# Sheet1.net
KiCad netlist of a schematic drawn in Altium Designer
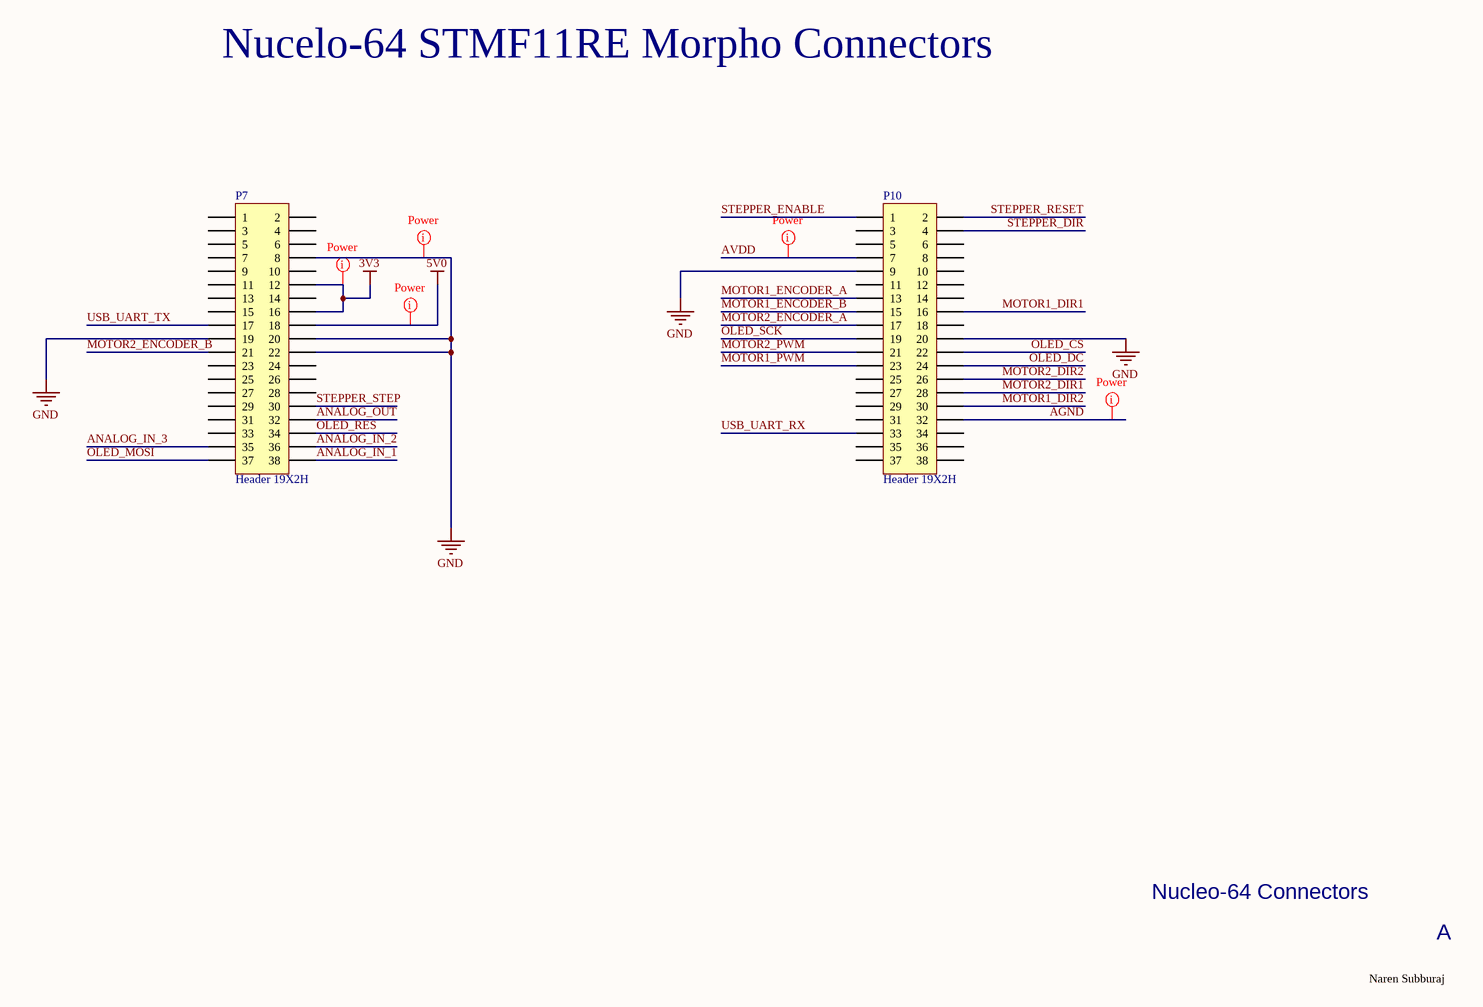
[diagram p0: Sheet1.SchDoc]

(export (version "E")
  (design (tool "Eeschema 10.0.6"))
  (components
    (comp (ref "P7")
      (value "Header 19X2H")
      (footprint "PPPC192LFBN-RC")
      (description "38 Position Header Connector 0.100in (2.54mm) Through Hole Gold")
      (fields (field (name "MPN") "PPPC192LFBN-RC"))
      (libsource (lib "esd_library") (part "Header 19X2H"))
    )
    (comp (ref "P10")
      (value "Header 19X2H")
      (footprint "PPPC192LFBN-RC")
      (description "38 Position Header Connector 0.100in (2.54mm) Through Hole Gold")
      (fields (field (name "MPN") "PPPC192LFBN-RC"))
      (libsource (lib "esd_library") (part "Header 19X2H"))
    )
  )
  (nets
    (net (code "1") (name "/AGND") (class "Default")
      (node (ref "P10") (pin "32") (pinfunction "32_32") (pintype "passive"))
    )
    (net (code "2") (name "/ANALOG_IN_1") (class "Default")
      (node (ref "P7") (pin "38") (pinfunction "38_38") (pintype "passive"))
    )
    (net (code "3") (name "/ANALOG_IN_2") (class "Default")
      (node (ref "P7") (pin "36") (pinfunction "36_36") (pintype "passive"))
    )
    (net (code "4") (name "/ANALOG_IN_3") (class "Default")
      (node (ref "P7") (pin "35") (pinfunction "35_35") (pintype "passive"))
    )
    (net (code "5") (name "/ANALOG_OUT") (class "Default")
      (node (ref "P7") (pin "32") (pinfunction "32_32") (pintype "passive"))
    )
    (net (code "6") (name "/AVDD") (class "Default")
      (node (ref "P10") (pin "7") (pinfunction "7_7") (pintype "passive"))
    )
    (net (code "7") (name "/MOTOR1_DIR1") (class "Default")
      (node (ref "P10") (pin "16") (pinfunction "16_16") (pintype "passive"))
    )
    (net (code "8") (name "/MOTOR1_DIR2") (class "Default")
      (node (ref "P10") (pin "30") (pinfunction "30_30") (pintype "passive"))
    )
    (net (code "9") (name "/MOTOR1_ENCODER_A") (class "Default")
      (node (ref "P10") (pin "13") (pinfunction "13_13") (pintype "passive"))
    )
    (net (code "10") (name "/MOTOR1_ENCODER_B") (class "Default")
      (node (ref "P10") (pin "15") (pinfunction "15_15") (pintype "passive"))
    )
    (net (code "11") (name "/MOTOR1_PWM") (class "Default")
      (node (ref "P10") (pin "23") (pinfunction "23_23") (pintype "passive"))
    )
    (net (code "12") (name "/MOTOR2_DIR1") (class "Default")
      (node (ref "P10") (pin "28") (pinfunction "28_28") (pintype "passive"))
    )
    (net (code "13") (name "/MOTOR2_DIR2") (class "Default")
      (node (ref "P10") (pin "26") (pinfunction "26_26") (pintype "passive"))
    )
    (net (code "14") (name "/MOTOR2_ENCODER_A") (class "Default")
      (node (ref "P10") (pin "17") (pinfunction "17_17") (pintype "passive"))
    )
    (net (code "15") (name "/MOTOR2_ENCODER_B") (class "Default")
      (node (ref "P7") (pin "21") (pinfunction "21_21") (pintype "passive"))
    )
    (net (code "16") (name "/MOTOR2_PWM") (class "Default")
      (node (ref "P10") (pin "21") (pinfunction "21_21") (pintype "passive"))
    )
    (net (code "17") (name "/OLED_CS") (class "Default")
      (node (ref "P10") (pin "22") (pinfunction "22_22") (pintype "passive"))
    )
    (net (code "18") (name "/OLED_DC") (class "Default")
      (node (ref "P10") (pin "24") (pinfunction "24_24") (pintype "passive"))
    )
    (net (code "19") (name "/OLED_MOSI") (class "Default")
      (node (ref "P7") (pin "37") (pinfunction "37_37") (pintype "passive"))
    )
    (net (code "20") (name "/OLED_RES") (class "Default")
      (node (ref "P7") (pin "34") (pinfunction "34_34") (pintype "passive"))
    )
    (net (code "21") (name "/OLED_SCK") (class "Default")
      (node (ref "P10") (pin "19") (pinfunction "19_19") (pintype "passive"))
    )
    (net (code "22") (name "/STEPPER_DIR") (class "Default")
      (node (ref "P10") (pin "4") (pinfunction "4_4") (pintype "passive"))
    )
    (net (code "23") (name "/STEPPER_ENABLE") (class "Default")
      (node (ref "P10") (pin "1") (pinfunction "1_1") (pintype "passive"))
    )
    (net (code "24") (name "/STEPPER_RESET") (class "Default")
      (node (ref "P10") (pin "2") (pinfunction "2_2") (pintype "passive"))
    )
    (net (code "25") (name "/STEPPER_STEP") (class "Default")
      (node (ref "P7") (pin "30") (pinfunction "30_30") (pintype "passive"))
    )
    (net (code "26") (name "/USB_UART_RX") (class "Default")
      (node (ref "P10") (pin "33") (pinfunction "33_33") (pintype "passive"))
    )
    (net (code "27") (name "/USB_UART_TX") (class "Default")
      (node (ref "P7") (pin "17") (pinfunction "17_17") (pintype "passive"))
    )
    (net (code "28") (name "3V3") (class "Default")
      (node (ref "P7") (pin "12") (pinfunction "12_12") (pintype "passive"))
      (node (ref "P7") (pin "16") (pinfunction "16_16") (pintype "passive"))
    )
    (net (code "29") (name "5V0") (class "Default")
      (node (ref "P7") (pin "18") (pinfunction "18_18") (pintype "passive"))
    )
    (net (code "30") (name "GND") (class "Default")
      (node (ref "P10") (pin "20") (pinfunction "20_20") (pintype "passive"))
      (node (ref "P10") (pin "9") (pinfunction "9_9") (pintype "passive"))
      (node (ref "P7") (pin "19") (pinfunction "19_19") (pintype "passive"))
      (node (ref "P7") (pin "20") (pinfunction "20_20") (pintype "passive"))
      (node (ref "P7") (pin "22") (pinfunction "22_22") (pintype "passive"))
      (node (ref "P7") (pin "8") (pinfunction "8_8") (pintype "passive"))
    )
    (net (code "31") (name "unconnected-(P7-Pad1)") (class "Default")
      (node (ref "P7") (pin "1") (pinfunction "1_1") (pintype "passive"))
    )
    (net (code "32") (name "unconnected-(P7-Pad2)") (class "Default")
      (node (ref "P7") (pin "2") (pinfunction "2_2") (pintype "passive"))
    )
    (net (code "33") (name "unconnected-(P7-Pad3)") (class "Default")
      (node (ref "P7") (pin "3") (pinfunction "3_3") (pintype "passive"))
    )
    (net (code "34") (name "unconnected-(P7-Pad4)") (class "Default")
      (node (ref "P7") (pin "4") (pinfunction "4_4") (pintype "passive"))
    )
    (net (code "35") (name "unconnected-(P7-Pad5)") (class "Default")
      (node (ref "P7") (pin "5") (pinfunction "5_5") (pintype "passive"))
    )
    (net (code "36") (name "unconnected-(P7-Pad6)") (class "Default")
      (node (ref "P7") (pin "6") (pinfunction "6_6") (pintype "passive"))
    )
    (net (code "37") (name "unconnected-(P7-Pad7)") (class "Default")
      (node (ref "P7") (pin "7") (pinfunction "7_7") (pintype "passive"))
    )
    (net (code "38") (name "unconnected-(P7-Pad9)") (class "Default")
      (node (ref "P7") (pin "9") (pinfunction "9_9") (pintype "passive"))
    )
    (net (code "39") (name "unconnected-(P7-Pad10)") (class "Default")
      (node (ref "P7") (pin "10") (pinfunction "10_10") (pintype "passive"))
    )
    (net (code "40") (name "unconnected-(P7-Pad11)") (class "Default")
      (node (ref "P7") (pin "11") (pinfunction "11_11") (pintype "passive"))
    )
    (net (code "41") (name "unconnected-(P7-Pad13)") (class "Default")
      (node (ref "P7") (pin "13") (pinfunction "13_13") (pintype "passive"))
    )
    (net (code "42") (name "unconnected-(P7-Pad14)") (class "Default")
      (node (ref "P7") (pin "14") (pinfunction "14_14") (pintype "passive"))
    )
    (net (code "43") (name "unconnected-(P7-Pad15)") (class "Default")
      (node (ref "P7") (pin "15") (pinfunction "15_15") (pintype "passive"))
    )
    (net (code "44") (name "unconnected-(P7-Pad23)") (class "Default")
      (node (ref "P7") (pin "23") (pinfunction "23_23") (pintype "passive"))
    )
    (net (code "45") (name "unconnected-(P7-Pad24)") (class "Default")
      (node (ref "P7") (pin "24") (pinfunction "24_24") (pintype "passive"))
    )
    (net (code "46") (name "unconnected-(P7-Pad25)") (class "Default")
      (node (ref "P7") (pin "25") (pinfunction "25_25") (pintype "passive"))
    )
    (net (code "47") (name "unconnected-(P7-Pad26)") (class "Default")
      (node (ref "P7") (pin "26") (pinfunction "26_26") (pintype "passive"))
    )
    (net (code "48") (name "unconnected-(P7-Pad27)") (class "Default")
      (node (ref "P7") (pin "27") (pinfunction "27_27") (pintype "passive"))
    )
    (net (code "49") (name "unconnected-(P7-Pad28)") (class "Default")
      (node (ref "P7") (pin "28") (pinfunction "28_28") (pintype "passive"))
    )
    (net (code "50") (name "unconnected-(P7-Pad29)") (class "Default")
      (node (ref "P7") (pin "29") (pinfunction "29_29") (pintype "passive"))
    )
    (net (code "51") (name "unconnected-(P7-Pad31)") (class "Default")
      (node (ref "P7") (pin "31") (pinfunction "31_31") (pintype "passive"))
    )
    (net (code "52") (name "unconnected-(P7-Pad33)") (class "Default")
      (node (ref "P7") (pin "33") (pinfunction "33_33") (pintype "passive"))
    )
    (net (code "53") (name "unconnected-(P10-Pad3)") (class "Default")
      (node (ref "P10") (pin "3") (pinfunction "3_3") (pintype "passive"))
    )
    (net (code "54") (name "unconnected-(P10-Pad5)") (class "Default")
      (node (ref "P10") (pin "5") (pinfunction "5_5") (pintype "passive"))
    )
    (net (code "55") (name "unconnected-(P10-Pad6)") (class "Default")
      (node (ref "P10") (pin "6") (pinfunction "6_6") (pintype "passive"))
    )
    (net (code "56") (name "unconnected-(P10-Pad8)") (class "Default")
      (node (ref "P10") (pin "8") (pinfunction "8_8") (pintype "passive"))
    )
    (net (code "57") (name "unconnected-(P10-Pad10)") (class "Default")
      (node (ref "P10") (pin "10") (pinfunction "10_10") (pintype "passive"))
    )
    (net (code "58") (name "unconnected-(P10-Pad11)") (class "Default")
      (node (ref "P10") (pin "11") (pinfunction "11_11") (pintype "passive"))
    )
    (net (code "59") (name "unconnected-(P10-Pad12)") (class "Default")
      (node (ref "P10") (pin "12") (pinfunction "12_12") (pintype "passive"))
    )
    (net (code "60") (name "unconnected-(P10-Pad14)") (class "Default")
      (node (ref "P10") (pin "14") (pinfunction "14_14") (pintype "passive"))
    )
    (net (code "61") (name "unconnected-(P10-Pad18)") (class "Default")
      (node (ref "P10") (pin "18") (pinfunction "18_18") (pintype "passive"))
    )
    (net (code "62") (name "unconnected-(P10-Pad25)") (class "Default")
      (node (ref "P10") (pin "25") (pinfunction "25_25") (pintype "passive"))
    )
    (net (code "63") (name "unconnected-(P10-Pad27)") (class "Default")
      (node (ref "P10") (pin "27") (pinfunction "27_27") (pintype "passive"))
    )
    (net (code "64") (name "unconnected-(P10-Pad29)") (class "Default")
      (node (ref "P10") (pin "29") (pinfunction "29_29") (pintype "passive"))
    )
    (net (code "65") (name "unconnected-(P10-Pad31)") (class "Default")
      (node (ref "P10") (pin "31") (pinfunction "31_31") (pintype "passive"))
    )
    (net (code "66") (name "unconnected-(P10-Pad34)") (class "Default")
      (node (ref "P10") (pin "34") (pinfunction "34_34") (pintype "passive"))
    )
    (net (code "67") (name "unconnected-(P10-Pad35)") (class "Default")
      (node (ref "P10") (pin "35") (pinfunction "35_35") (pintype "passive"))
    )
    (net (code "68") (name "unconnected-(P10-Pad36)") (class "Default")
      (node (ref "P10") (pin "36") (pinfunction "36_36") (pintype "passive"))
    )
    (net (code "69") (name "unconnected-(P10-Pad37)") (class "Default")
      (node (ref "P10") (pin "37") (pinfunction "37_37") (pintype "passive"))
    )
    (net (code "70") (name "unconnected-(P10-Pad38)") (class "Default")
      (node (ref "P10") (pin "38") (pinfunction "38_38") (pintype "passive"))
    )
  )
)
